# RelaisAdOn.net
KiCad netlist of a schematic drawn in EAGLE
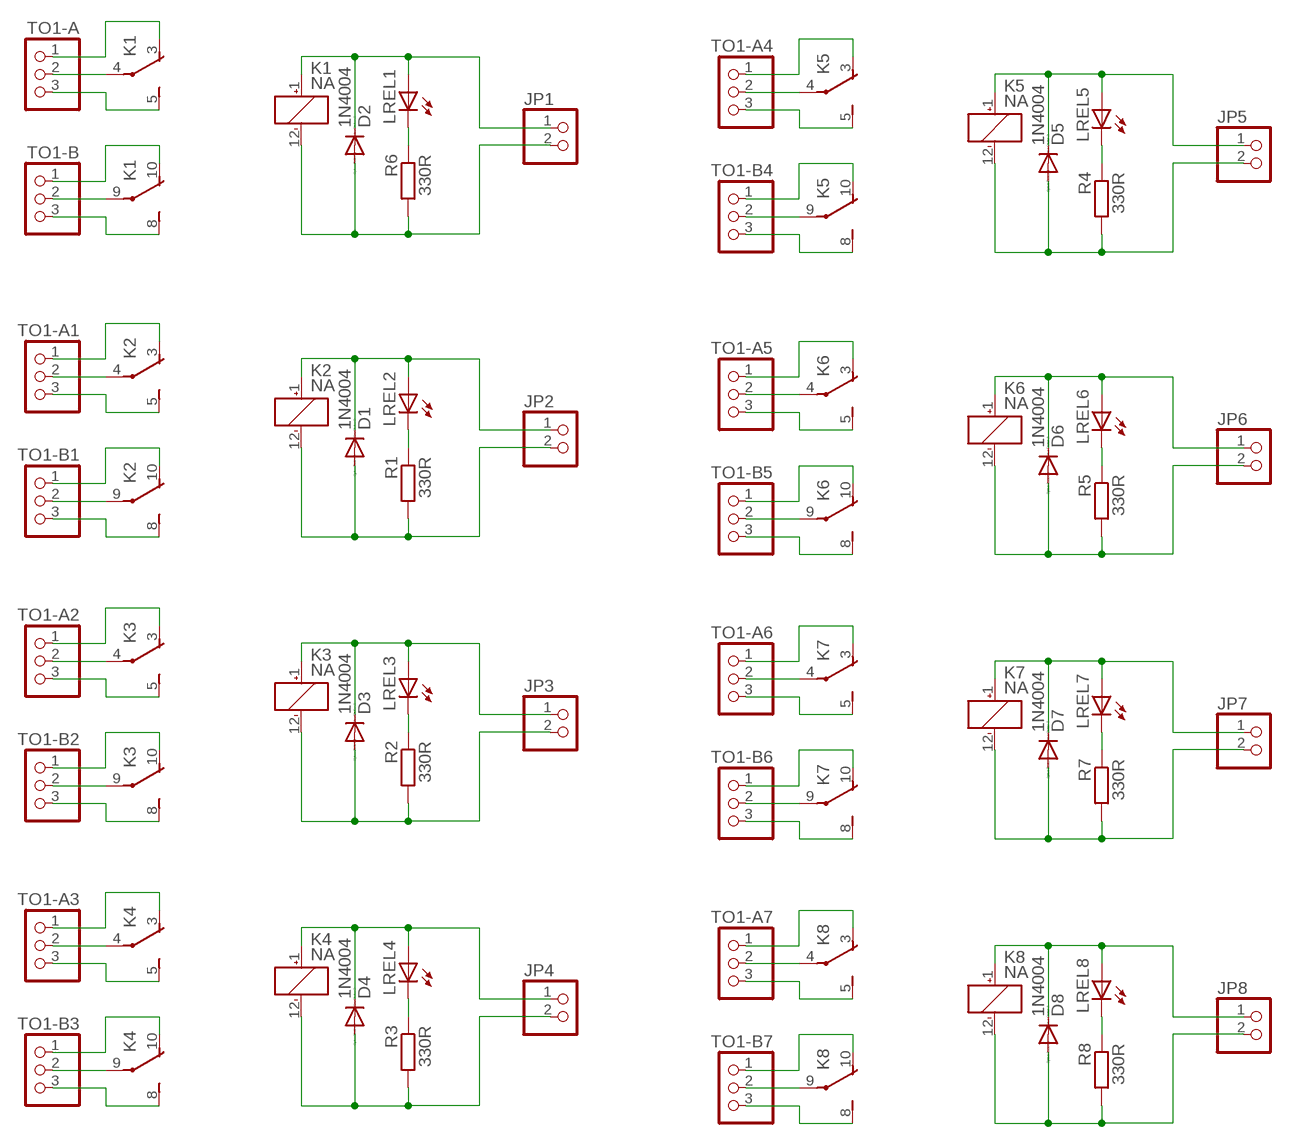
[diagram p0: schematic, sheet 1]

(export (version "E")
  (design (tool "Eeschema 10.0.6"))
  (components
    (comp (ref "D1")
      (value "1N4004")
      (footprint "eagle-import:DO41-10")
      (libsource (lib "eagle-import") (part "1N4004"))
    )
    (comp (ref "D2")
      (value "1N4004")
      (footprint "eagle-import:DO41-10")
      (libsource (lib "eagle-import") (part "1N4004"))
    )
    (comp (ref "D3")
      (value "1N4004")
      (footprint "eagle-import:DO41-10")
      (libsource (lib "eagle-import") (part "1N4004"))
    )
    (comp (ref "D4")
      (value "1N4004")
      (footprint "eagle-import:DO41-10")
      (libsource (lib "eagle-import") (part "1N4004"))
    )
    (comp (ref "D5")
      (value "1N4004")
      (footprint "eagle-import:DO41-10")
      (libsource (lib "eagle-import") (part "1N4004"))
    )
    (comp (ref "D6")
      (value "1N4004")
      (footprint "eagle-import:DO41-10")
      (libsource (lib "eagle-import") (part "1N4004"))
    )
    (comp (ref "D7")
      (value "1N4004")
      (footprint "eagle-import:DO41-10")
      (libsource (lib "eagle-import") (part "1N4004"))
    )
    (comp (ref "D8")
      (value "1N4004")
      (footprint "eagle-import:DO41-10")
      (libsource (lib "eagle-import") (part "1N4004"))
    )
    (comp (ref "JP1")
      (value "PINHD-1X2")
      (footprint "eagle-import:1X02")
      (libsource (lib "eagle-import") (part "PINHD-1X2"))
    )
    (comp (ref "JP2")
      (value "PINHD-1X2")
      (footprint "eagle-import:1X02")
      (libsource (lib "eagle-import") (part "PINHD-1X2"))
    )
    (comp (ref "JP3")
      (value "PINHD-1X2")
      (footprint "eagle-import:1X02")
      (libsource (lib "eagle-import") (part "PINHD-1X2"))
    )
    (comp (ref "JP4")
      (value "PINHD-1X2")
      (footprint "eagle-import:1X02")
      (libsource (lib "eagle-import") (part "PINHD-1X2"))
    )
    (comp (ref "JP5")
      (value "PINHD-1X2")
      (footprint "eagle-import:1X02")
      (libsource (lib "eagle-import") (part "PINHD-1X2"))
    )
    (comp (ref "JP6")
      (value "PINHD-1X2")
      (footprint "eagle-import:1X02")
      (libsource (lib "eagle-import") (part "PINHD-1X2"))
    )
    (comp (ref "JP7")
      (value "PINHD-1X2")
      (footprint "eagle-import:1X02")
      (libsource (lib "eagle-import") (part "PINHD-1X2"))
    )
    (comp (ref "JP8")
      (value "PINHD-1X2")
      (footprint "eagle-import:1X02")
      (libsource (lib "eagle-import") (part "PINHD-1X2"))
    )
    (comp (ref "K1") (value "NA") (footprint "eagle-import:NA") (libsource (lib "eagle-import") (part "NA")))
    (comp (ref "K2") (value "NA") (footprint "eagle-import:NA") (libsource (lib "eagle-import") (part "NA")))
    (comp (ref "K3") (value "NA") (footprint "eagle-import:NA") (libsource (lib "eagle-import") (part "NA")))
    (comp (ref "K4") (value "NA") (footprint "eagle-import:NA") (libsource (lib "eagle-import") (part "NA")))
    (comp (ref "K5") (value "NA") (footprint "eagle-import:NA") (libsource (lib "eagle-import") (part "NA")))
    (comp (ref "K6") (value "NA") (footprint "eagle-import:NA") (libsource (lib "eagle-import") (part "NA")))
    (comp (ref "K7") (value "NA") (footprint "eagle-import:NA") (libsource (lib "eagle-import") (part "NA")))
    (comp (ref "K8") (value "NA") (footprint "eagle-import:NA") (libsource (lib "eagle-import") (part "NA")))
    (comp (ref "LREL1")
      (value "LED3MM")
      (footprint "eagle-import:LED3MM")
      (libsource (lib "eagle-import") (part "LED3MM"))
    )
    (comp (ref "LREL2")
      (value "LED3MM")
      (footprint "eagle-import:LED3MM")
      (libsource (lib "eagle-import") (part "LED3MM"))
    )
    (comp (ref "LREL3")
      (value "LED3MM")
      (footprint "eagle-import:LED3MM")
      (libsource (lib "eagle-import") (part "LED3MM"))
    )
    (comp (ref "LREL4")
      (value "LED3MM")
      (footprint "eagle-import:LED3MM")
      (libsource (lib "eagle-import") (part "LED3MM"))
    )
    (comp (ref "LREL5")
      (value "LED3MM")
      (footprint "eagle-import:LED3MM")
      (libsource (lib "eagle-import") (part "LED3MM"))
    )
    (comp (ref "LREL6")
      (value "LED3MM")
      (footprint "eagle-import:LED3MM")
      (libsource (lib "eagle-import") (part "LED3MM"))
    )
    (comp (ref "LREL7")
      (value "LED3MM")
      (footprint "eagle-import:LED3MM")
      (libsource (lib "eagle-import") (part "LED3MM"))
    )
    (comp (ref "LREL8")
      (value "LED3MM")
      (footprint "eagle-import:LED3MM")
      (libsource (lib "eagle-import") (part "LED3MM"))
    )
    (comp (ref "R1")
      (value "330R")
      (footprint "eagle-import:0207_7")
      (libsource (lib "eagle-import") (part "R-EU_0207/7"))
    )
    (comp (ref "R2")
      (value "330R")
      (footprint "eagle-import:0207_7")
      (libsource (lib "eagle-import") (part "R-EU_0207/7"))
    )
    (comp (ref "R3")
      (value "330R")
      (footprint "eagle-import:0207_7")
      (libsource (lib "eagle-import") (part "R-EU_0207/7"))
    )
    (comp (ref "R4")
      (value "330R")
      (footprint "eagle-import:0207_7")
      (libsource (lib "eagle-import") (part "R-EU_0207/7"))
    )
    (comp (ref "R5")
      (value "330R")
      (footprint "eagle-import:0207_7")
      (libsource (lib "eagle-import") (part "R-EU_0207/7"))
    )
    (comp (ref "R6")
      (value "330R")
      (footprint "eagle-import:0207_7")
      (libsource (lib "eagle-import") (part "R-EU_0207/7"))
    )
    (comp (ref "R7")
      (value "330R")
      (footprint "eagle-import:0207_7")
      (libsource (lib "eagle-import") (part "R-EU_0207/7"))
    )
    (comp (ref "R8")
      (value "330R")
      (footprint "eagle-import:0207_7")
      (libsource (lib "eagle-import") (part "R-EU_0207/7"))
    )
    (comp (ref "TO1-A")
      (value "PINHD-1X3")
      (footprint "eagle-import:1X03")
      (libsource (lib "eagle-import") (part "PINHD-1X3"))
    )
    (comp (ref "TO1-A1")
      (value "PINHD-1X3")
      (footprint "eagle-import:1X03")
      (libsource (lib "eagle-import") (part "PINHD-1X3"))
    )
    (comp (ref "TO1-A2")
      (value "PINHD-1X3")
      (footprint "eagle-import:1X03")
      (libsource (lib "eagle-import") (part "PINHD-1X3"))
    )
    (comp (ref "TO1-A3")
      (value "PINHD-1X3")
      (footprint "eagle-import:1X03")
      (libsource (lib "eagle-import") (part "PINHD-1X3"))
    )
    (comp (ref "TO1-A4")
      (value "PINHD-1X3")
      (footprint "eagle-import:1X03")
      (libsource (lib "eagle-import") (part "PINHD-1X3"))
    )
    (comp (ref "TO1-A5")
      (value "PINHD-1X3")
      (footprint "eagle-import:1X03")
      (libsource (lib "eagle-import") (part "PINHD-1X3"))
    )
    (comp (ref "TO1-A6")
      (value "PINHD-1X3")
      (footprint "eagle-import:1X03")
      (libsource (lib "eagle-import") (part "PINHD-1X3"))
    )
    (comp (ref "TO1-A7")
      (value "PINHD-1X3")
      (footprint "eagle-import:1X03")
      (libsource (lib "eagle-import") (part "PINHD-1X3"))
    )
    (comp (ref "TO1-B")
      (value "PINHD-1X3")
      (footprint "eagle-import:1X03")
      (libsource (lib "eagle-import") (part "PINHD-1X3"))
    )
    (comp (ref "TO1-B1")
      (value "PINHD-1X3")
      (footprint "eagle-import:1X03")
      (libsource (lib "eagle-import") (part "PINHD-1X3"))
    )
    (comp (ref "TO1-B2")
      (value "PINHD-1X3")
      (footprint "eagle-import:1X03")
      (libsource (lib "eagle-import") (part "PINHD-1X3"))
    )
    (comp (ref "TO1-B3")
      (value "PINHD-1X3")
      (footprint "eagle-import:1X03")
      (libsource (lib "eagle-import") (part "PINHD-1X3"))
    )
    (comp (ref "TO1-B4")
      (value "PINHD-1X3")
      (footprint "eagle-import:1X03")
      (libsource (lib "eagle-import") (part "PINHD-1X3"))
    )
    (comp (ref "TO1-B5")
      (value "PINHD-1X3")
      (footprint "eagle-import:1X03")
      (libsource (lib "eagle-import") (part "PINHD-1X3"))
    )
    (comp (ref "TO1-B6")
      (value "PINHD-1X3")
      (footprint "eagle-import:1X03")
      (libsource (lib "eagle-import") (part "PINHD-1X3"))
    )
    (comp (ref "TO1-B7")
      (value "PINHD-1X3")
      (footprint "eagle-import:1X03")
      (libsource (lib "eagle-import") (part "PINHD-1X3"))
    )
  )
  (nets
    (net (code "1") (name "Net-(K1A-+)") (class "Default")
      (node (ref "D2") (pin "C") (pinfunction "C_C") (pintype "passive"))
      (node (ref "JP1") (pin "1") (pinfunction "1_1") (pintype "passive"))
      (node (ref "K1") (pin "1") (pinfunction "+_1") (pintype "passive"))
      (node (ref "LREL1") (pin "A") (pinfunction "A_A") (pintype "passive"))
    )
    (net (code "2") (name "Net-(K1A--)") (class "Default")
      (node (ref "D2") (pin "A") (pinfunction "A_A") (pintype "passive"))
      (node (ref "JP1") (pin "2") (pinfunction "2_2") (pintype "passive"))
      (node (ref "K1") (pin "12") (pinfunction "-_12") (pintype "passive"))
      (node (ref "R6") (pin "2") (pinfunction "2_2") (pintype "passive"))
    )
    (net (code "3") (name "Net-(K1B-O)") (class "Default")
      (node (ref "K1") (pin "3") (pinfunction "O_3") (pintype "passive"))
      (node (ref "TO1-A") (pin "1") (pinfunction "1_1") (pintype "passive"))
    )
    (net (code "4") (name "Net-(K1B-P)") (class "Default")
      (node (ref "K1") (pin "4") (pinfunction "P_4") (pintype "passive"))
      (node (ref "TO1-A") (pin "2") (pinfunction "2_2") (pintype "passive"))
    )
    (net (code "5") (name "Net-(K1B-S)") (class "Default")
      (node (ref "K1") (pin "5") (pinfunction "S_5") (pintype "passive"))
      (node (ref "TO1-A") (pin "3") (pinfunction "3_3") (pintype "passive"))
    )
    (net (code "6") (name "Net-(K1C-O)") (class "Default")
      (node (ref "K1") (pin "10") (pinfunction "O_10") (pintype "passive"))
      (node (ref "TO1-B") (pin "1") (pinfunction "1_1") (pintype "passive"))
    )
    (net (code "7") (name "Net-(K1C-P)") (class "Default")
      (node (ref "K1") (pin "9") (pinfunction "P_9") (pintype "passive"))
      (node (ref "TO1-B") (pin "2") (pinfunction "2_2") (pintype "passive"))
    )
    (net (code "8") (name "Net-(K1C-S)") (class "Default")
      (node (ref "K1") (pin "8") (pinfunction "S_8") (pintype "passive"))
      (node (ref "TO1-B") (pin "3") (pinfunction "3_3") (pintype "passive"))
    )
    (net (code "9") (name "Net-(K2A-+)") (class "Default")
      (node (ref "D1") (pin "C") (pinfunction "C_C") (pintype "passive"))
      (node (ref "JP2") (pin "1") (pinfunction "1_1") (pintype "passive"))
      (node (ref "K2") (pin "1") (pinfunction "+_1") (pintype "passive"))
      (node (ref "LREL2") (pin "A") (pinfunction "A_A") (pintype "passive"))
    )
    (net (code "10") (name "Net-(K2A--)") (class "Default")
      (node (ref "D1") (pin "A") (pinfunction "A_A") (pintype "passive"))
      (node (ref "JP2") (pin "2") (pinfunction "2_2") (pintype "passive"))
      (node (ref "K2") (pin "12") (pinfunction "-_12") (pintype "passive"))
      (node (ref "R1") (pin "2") (pinfunction "2_2") (pintype "passive"))
    )
    (net (code "11") (name "Net-(K2B-O)") (class "Default")
      (node (ref "K2") (pin "3") (pinfunction "O_3") (pintype "passive"))
      (node (ref "TO1-A1") (pin "1") (pinfunction "1_1") (pintype "passive"))
    )
    (net (code "12") (name "Net-(K2B-P)") (class "Default")
      (node (ref "K2") (pin "4") (pinfunction "P_4") (pintype "passive"))
      (node (ref "TO1-A1") (pin "2") (pinfunction "2_2") (pintype "passive"))
    )
    (net (code "13") (name "Net-(K2B-S)") (class "Default")
      (node (ref "K2") (pin "5") (pinfunction "S_5") (pintype "passive"))
      (node (ref "TO1-A1") (pin "3") (pinfunction "3_3") (pintype "passive"))
    )
    (net (code "14") (name "Net-(K2C-O)") (class "Default")
      (node (ref "K2") (pin "10") (pinfunction "O_10") (pintype "passive"))
      (node (ref "TO1-B1") (pin "1") (pinfunction "1_1") (pintype "passive"))
    )
    (net (code "15") (name "Net-(K2C-P)") (class "Default")
      (node (ref "K2") (pin "9") (pinfunction "P_9") (pintype "passive"))
      (node (ref "TO1-B1") (pin "2") (pinfunction "2_2") (pintype "passive"))
    )
    (net (code "16") (name "Net-(K2C-S)") (class "Default")
      (node (ref "K2") (pin "8") (pinfunction "S_8") (pintype "passive"))
      (node (ref "TO1-B1") (pin "3") (pinfunction "3_3") (pintype "passive"))
    )
    (net (code "17") (name "Net-(K3A-+)") (class "Default")
      (node (ref "D3") (pin "C") (pinfunction "C_C") (pintype "passive"))
      (node (ref "JP3") (pin "1") (pinfunction "1_1") (pintype "passive"))
      (node (ref "K3") (pin "1") (pinfunction "+_1") (pintype "passive"))
      (node (ref "LREL3") (pin "A") (pinfunction "A_A") (pintype "passive"))
    )
    (net (code "18") (name "Net-(K3A--)") (class "Default")
      (node (ref "D3") (pin "A") (pinfunction "A_A") (pintype "passive"))
      (node (ref "JP3") (pin "2") (pinfunction "2_2") (pintype "passive"))
      (node (ref "K3") (pin "12") (pinfunction "-_12") (pintype "passive"))
      (node (ref "R2") (pin "2") (pinfunction "2_2") (pintype "passive"))
    )
    (net (code "19") (name "Net-(K3B-O)") (class "Default")
      (node (ref "K3") (pin "3") (pinfunction "O_3") (pintype "passive"))
      (node (ref "TO1-A2") (pin "1") (pinfunction "1_1") (pintype "passive"))
    )
    (net (code "20") (name "Net-(K3B-P)") (class "Default")
      (node (ref "K3") (pin "4") (pinfunction "P_4") (pintype "passive"))
      (node (ref "TO1-A2") (pin "2") (pinfunction "2_2") (pintype "passive"))
    )
    (net (code "21") (name "Net-(K3B-S)") (class "Default")
      (node (ref "K3") (pin "5") (pinfunction "S_5") (pintype "passive"))
      (node (ref "TO1-A2") (pin "3") (pinfunction "3_3") (pintype "passive"))
    )
    (net (code "22") (name "Net-(K3C-O)") (class "Default")
      (node (ref "K3") (pin "10") (pinfunction "O_10") (pintype "passive"))
      (node (ref "TO1-B2") (pin "1") (pinfunction "1_1") (pintype "passive"))
    )
    (net (code "23") (name "Net-(K3C-P)") (class "Default")
      (node (ref "K3") (pin "9") (pinfunction "P_9") (pintype "passive"))
      (node (ref "TO1-B2") (pin "2") (pinfunction "2_2") (pintype "passive"))
    )
    (net (code "24") (name "Net-(K3C-S)") (class "Default")
      (node (ref "K3") (pin "8") (pinfunction "S_8") (pintype "passive"))
      (node (ref "TO1-B2") (pin "3") (pinfunction "3_3") (pintype "passive"))
    )
    (net (code "25") (name "Net-(K4A-+)") (class "Default")
      (node (ref "D4") (pin "C") (pinfunction "C_C") (pintype "passive"))
      (node (ref "JP4") (pin "1") (pinfunction "1_1") (pintype "passive"))
      (node (ref "K4") (pin "1") (pinfunction "+_1") (pintype "passive"))
      (node (ref "LREL4") (pin "A") (pinfunction "A_A") (pintype "passive"))
    )
    (net (code "26") (name "Net-(K4A--)") (class "Default")
      (node (ref "D4") (pin "A") (pinfunction "A_A") (pintype "passive"))
      (node (ref "JP4") (pin "2") (pinfunction "2_2") (pintype "passive"))
      (node (ref "K4") (pin "12") (pinfunction "-_12") (pintype "passive"))
      (node (ref "R3") (pin "2") (pinfunction "2_2") (pintype "passive"))
    )
    (net (code "27") (name "Net-(K4B-O)") (class "Default")
      (node (ref "K4") (pin "3") (pinfunction "O_3") (pintype "passive"))
      (node (ref "TO1-A3") (pin "1") (pinfunction "1_1") (pintype "passive"))
    )
    (net (code "28") (name "Net-(K4B-P)") (class "Default")
      (node (ref "K4") (pin "4") (pinfunction "P_4") (pintype "passive"))
      (node (ref "TO1-A3") (pin "2") (pinfunction "2_2") (pintype "passive"))
    )
    (net (code "29") (name "Net-(K4B-S)") (class "Default")
      (node (ref "K4") (pin "5") (pinfunction "S_5") (pintype "passive"))
      (node (ref "TO1-A3") (pin "3") (pinfunction "3_3") (pintype "passive"))
    )
    (net (code "30") (name "Net-(K4C-O)") (class "Default")
      (node (ref "K4") (pin "10") (pinfunction "O_10") (pintype "passive"))
      (node (ref "TO1-B3") (pin "1") (pinfunction "1_1") (pintype "passive"))
    )
    (net (code "31") (name "Net-(K4C-P)") (class "Default")
      (node (ref "K4") (pin "9") (pinfunction "P_9") (pintype "passive"))
      (node (ref "TO1-B3") (pin "2") (pinfunction "2_2") (pintype "passive"))
    )
    (net (code "32") (name "Net-(K4C-S)") (class "Default")
      (node (ref "K4") (pin "8") (pinfunction "S_8") (pintype "passive"))
      (node (ref "TO1-B3") (pin "3") (pinfunction "3_3") (pintype "passive"))
    )
    (net (code "33") (name "Net-(K5A-+)") (class "Default")
      (node (ref "D5") (pin "C") (pinfunction "C_C") (pintype "passive"))
      (node (ref "JP5") (pin "1") (pinfunction "1_1") (pintype "passive"))
      (node (ref "K5") (pin "1") (pinfunction "+_1") (pintype "passive"))
      (node (ref "LREL5") (pin "A") (pinfunction "A_A") (pintype "passive"))
    )
    (net (code "34") (name "Net-(K5A--)") (class "Default")
      (node (ref "D5") (pin "A") (pinfunction "A_A") (pintype "passive"))
      (node (ref "JP5") (pin "2") (pinfunction "2_2") (pintype "passive"))
      (node (ref "K5") (pin "12") (pinfunction "-_12") (pintype "passive"))
      (node (ref "R4") (pin "2") (pinfunction "2_2") (pintype "passive"))
    )
    (net (code "35") (name "Net-(K5B-O)") (class "Default")
      (node (ref "K5") (pin "3") (pinfunction "O_3") (pintype "passive"))
      (node (ref "TO1-A4") (pin "1") (pinfunction "1_1") (pintype "passive"))
    )
    (net (code "36") (name "Net-(K5B-P)") (class "Default")
      (node (ref "K5") (pin "4") (pinfunction "P_4") (pintype "passive"))
      (node (ref "TO1-A4") (pin "2") (pinfunction "2_2") (pintype "passive"))
    )
    (net (code "37") (name "Net-(K5B-S)") (class "Default")
      (node (ref "K5") (pin "5") (pinfunction "S_5") (pintype "passive"))
      (node (ref "TO1-A4") (pin "3") (pinfunction "3_3") (pintype "passive"))
    )
    (net (code "38") (name "Net-(K5C-O)") (class "Default")
      (node (ref "K5") (pin "10") (pinfunction "O_10") (pintype "passive"))
      (node (ref "TO1-B4") (pin "1") (pinfunction "1_1") (pintype "passive"))
    )
    (net (code "39") (name "Net-(K5C-P)") (class "Default")
      (node (ref "K5") (pin "9") (pinfunction "P_9") (pintype "passive"))
      (node (ref "TO1-B4") (pin "2") (pinfunction "2_2") (pintype "passive"))
    )
    (net (code "40") (name "Net-(K5C-S)") (class "Default")
      (node (ref "K5") (pin "8") (pinfunction "S_8") (pintype "passive"))
      (node (ref "TO1-B4") (pin "3") (pinfunction "3_3") (pintype "passive"))
    )
    (net (code "41") (name "Net-(K6A-+)") (class "Default")
      (node (ref "D6") (pin "C") (pinfunction "C_C") (pintype "passive"))
      (node (ref "JP6") (pin "1") (pinfunction "1_1") (pintype "passive"))
      (node (ref "K6") (pin "1") (pinfunction "+_1") (pintype "passive"))
      (node (ref "LREL6") (pin "A") (pinfunction "A_A") (pintype "passive"))
    )
    (net (code "42") (name "Net-(K6A--)") (class "Default")
      (node (ref "D6") (pin "A") (pinfunction "A_A") (pintype "passive"))
      (node (ref "JP6") (pin "2") (pinfunction "2_2") (pintype "passive"))
      (node (ref "K6") (pin "12") (pinfunction "-_12") (pintype "passive"))
      (node (ref "R5") (pin "2") (pinfunction "2_2") (pintype "passive"))
    )
    (net (code "43") (name "Net-(K6B-O)") (class "Default")
      (node (ref "K6") (pin "3") (pinfunction "O_3") (pintype "passive"))
      (node (ref "TO1-A5") (pin "1") (pinfunction "1_1") (pintype "passive"))
    )
    (net (code "44") (name "Net-(K6B-P)") (class "Default")
      (node (ref "K6") (pin "4") (pinfunction "P_4") (pintype "passive"))
      (node (ref "TO1-A5") (pin "2") (pinfunction "2_2") (pintype "passive"))
    )
    (net (code "45") (name "Net-(K6B-S)") (class "Default")
      (node (ref "K6") (pin "5") (pinfunction "S_5") (pintype "passive"))
      (node (ref "TO1-A5") (pin "3") (pinfunction "3_3") (pintype "passive"))
    )
    (net (code "46") (name "Net-(K6C-O)") (class "Default")
      (node (ref "K6") (pin "10") (pinfunction "O_10") (pintype "passive"))
      (node (ref "TO1-B5") (pin "1") (pinfunction "1_1") (pintype "passive"))
    )
    (net (code "47") (name "Net-(K6C-P)") (class "Default")
      (node (ref "K6") (pin "9") (pinfunction "P_9") (pintype "passive"))
      (node (ref "TO1-B5") (pin "2") (pinfunction "2_2") (pintype "passive"))
    )
    (net (code "48") (name "Net-(K6C-S)") (class "Default")
      (node (ref "K6") (pin "8") (pinfunction "S_8") (pintype "passive"))
      (node (ref "TO1-B5") (pin "3") (pinfunction "3_3") (pintype "passive"))
    )
    (net (code "49") (name "Net-(K7A-+)") (class "Default")
      (node (ref "D7") (pin "C") (pinfunction "C_C") (pintype "passive"))
      (node (ref "JP7") (pin "1") (pinfunction "1_1") (pintype "passive"))
      (node (ref "K7") (pin "1") (pinfunction "+_1") (pintype "passive"))
      (node (ref "LREL7") (pin "A") (pinfunction "A_A") (pintype "passive"))
    )
    (net (code "50") (name "Net-(K7A--)") (class "Default")
      (node (ref "D7") (pin "A") (pinfunction "A_A") (pintype "passive"))
      (node (ref "JP7") (pin "2") (pinfunction "2_2") (pintype "passive"))
      (node (ref "K7") (pin "12") (pinfunction "-_12") (pintype "passive"))
      (node (ref "R7") (pin "2") (pinfunction "2_2") (pintype "passive"))
    )
    (net (code "51") (name "Net-(K7B-O)") (class "Default")
      (node (ref "K7") (pin "3") (pinfunction "O_3") (pintype "passive"))
      (node (ref "TO1-A6") (pin "1") (pinfunction "1_1") (pintype "passive"))
    )
    (net (code "52") (name "Net-(K7B-P)") (class "Default")
      (node (ref "K7") (pin "4") (pinfunction "P_4") (pintype "passive"))
      (node (ref "TO1-A6") (pin "2") (pinfunction "2_2") (pintype "passive"))
    )
    (net (code "53") (name "Net-(K7B-S)") (class "Default")
      (node (ref "K7") (pin "5") (pinfunction "S_5") (pintype "passive"))
      (node (ref "TO1-A6") (pin "3") (pinfunction "3_3") (pintype "passive"))
    )
    (net (code "54") (name "Net-(K7C-O)") (class "Default")
      (node (ref "K7") (pin "10") (pinfunction "O_10") (pintype "passive"))
      (node (ref "TO1-B6") (pin "1") (pinfunction "1_1") (pintype "passive"))
    )
    (net (code "55") (name "Net-(K7C-P)") (class "Default")
      (node (ref "K7") (pin "9") (pinfunction "P_9") (pintype "passive"))
      (node (ref "TO1-B6") (pin "2") (pinfunction "2_2") (pintype "passive"))
    )
    (net (code "56") (name "Net-(K7C-S)") (class "Default")
      (node (ref "K7") (pin "8") (pinfunction "S_8") (pintype "passive"))
      (node (ref "TO1-B6") (pin "3") (pinfunction "3_3") (pintype "passive"))
    )
    (net (code "57") (name "Net-(K8A-+)") (class "Default")
      (node (ref "D8") (pin "C") (pinfunction "C_C") (pintype "passive"))
      (node (ref "JP8") (pin "1") (pinfunction "1_1") (pintype "passive"))
      (node (ref "K8") (pin "1") (pinfunction "+_1") (pintype "passive"))
      (node (ref "LREL8") (pin "A") (pinfunction "A_A") (pintype "passive"))
    )
    (net (code "58") (name "Net-(K8A--)") (class "Default")
      (node (ref "D8") (pin "A") (pinfunction "A_A") (pintype "passive"))
      (node (ref "JP8") (pin "2") (pinfunction "2_2") (pintype "passive"))
      (node (ref "K8") (pin "12") (pinfunction "-_12") (pintype "passive"))
      (node (ref "R8") (pin "2") (pinfunction "2_2") (pintype "passive"))
    )
    (net (code "59") (name "Net-(K8B-O)") (class "Default")
      (node (ref "K8") (pin "3") (pinfunction "O_3") (pintype "passive"))
      (node (ref "TO1-A7") (pin "1") (pinfunction "1_1") (pintype "passive"))
    )
    (net (code "60") (name "Net-(K8B-P)") (class "Default")
      (node (ref "K8") (pin "4") (pinfunction "P_4") (pintype "passive"))
      (node (ref "TO1-A7") (pin "2") (pinfunction "2_2") (pintype "passive"))
    )
    (net (code "61") (name "Net-(K8B-S)") (class "Default")
      (node (ref "K8") (pin "5") (pinfunction "S_5") (pintype "passive"))
      (node (ref "TO1-A7") (pin "3") (pinfunction "3_3") (pintype "passive"))
    )
    (net (code "62") (name "Net-(K8C-O)") (class "Default")
      (node (ref "K8") (pin "10") (pinfunction "O_10") (pintype "passive"))
      (node (ref "TO1-B7") (pin "1") (pinfunction "1_1") (pintype "passive"))
    )
    (net (code "63") (name "Net-(K8C-P)") (class "Default")
      (node (ref "K8") (pin "9") (pinfunction "P_9") (pintype "passive"))
      (node (ref "TO1-B7") (pin "2") (pinfunction "2_2") (pintype "passive"))
    )
    (net (code "64") (name "Net-(K8C-S)") (class "Default")
      (node (ref "K8") (pin "8") (pinfunction "S_8") (pintype "passive"))
      (node (ref "TO1-B7") (pin "3") (pinfunction "3_3") (pintype "passive"))
    )
    (net (code "65") (name "Net-(LREL1-C)") (class "Default")
      (node (ref "LREL1") (pin "K") (pinfunction "C_K") (pintype "passive"))
      (node (ref "R6") (pin "1") (pinfunction "1_1") (pintype "passive"))
    )
    (net (code "66") (name "Net-(LREL2-C)") (class "Default")
      (node (ref "LREL2") (pin "K") (pinfunction "C_K") (pintype "passive"))
      (node (ref "R1") (pin "1") (pinfunction "1_1") (pintype "passive"))
    )
    (net (code "67") (name "Net-(LREL3-C)") (class "Default")
      (node (ref "LREL3") (pin "K") (pinfunction "C_K") (pintype "passive"))
      (node (ref "R2") (pin "1") (pinfunction "1_1") (pintype "passive"))
    )
    (net (code "68") (name "Net-(LREL4-C)") (class "Default")
      (node (ref "LREL4") (pin "K") (pinfunction "C_K") (pintype "passive"))
      (node (ref "R3") (pin "1") (pinfunction "1_1") (pintype "passive"))
    )
    (net (code "69") (name "Net-(LREL5-C)") (class "Default")
      (node (ref "LREL5") (pin "K") (pinfunction "C_K") (pintype "passive"))
      (node (ref "R4") (pin "1") (pinfunction "1_1") (pintype "passive"))
    )
    (net (code "70") (name "Net-(LREL6-C)") (class "Default")
      (node (ref "LREL6") (pin "K") (pinfunction "C_K") (pintype "passive"))
      (node (ref "R5") (pin "1") (pinfunction "1_1") (pintype "passive"))
    )
    (net (code "71") (name "Net-(LREL7-C)") (class "Default")
      (node (ref "LREL7") (pin "K") (pinfunction "C_K") (pintype "passive"))
      (node (ref "R7") (pin "1") (pinfunction "1_1") (pintype "passive"))
    )
    (net (code "72") (name "Net-(LREL8-C)") (class "Default")
      (node (ref "LREL8") (pin "K") (pinfunction "C_K") (pintype "passive"))
      (node (ref "R8") (pin "1") (pinfunction "1_1") (pintype "passive"))
    )
  )
)
